# Canbus_controller_-_4.net
KiCad netlist of a schematic drawn in EAGLE
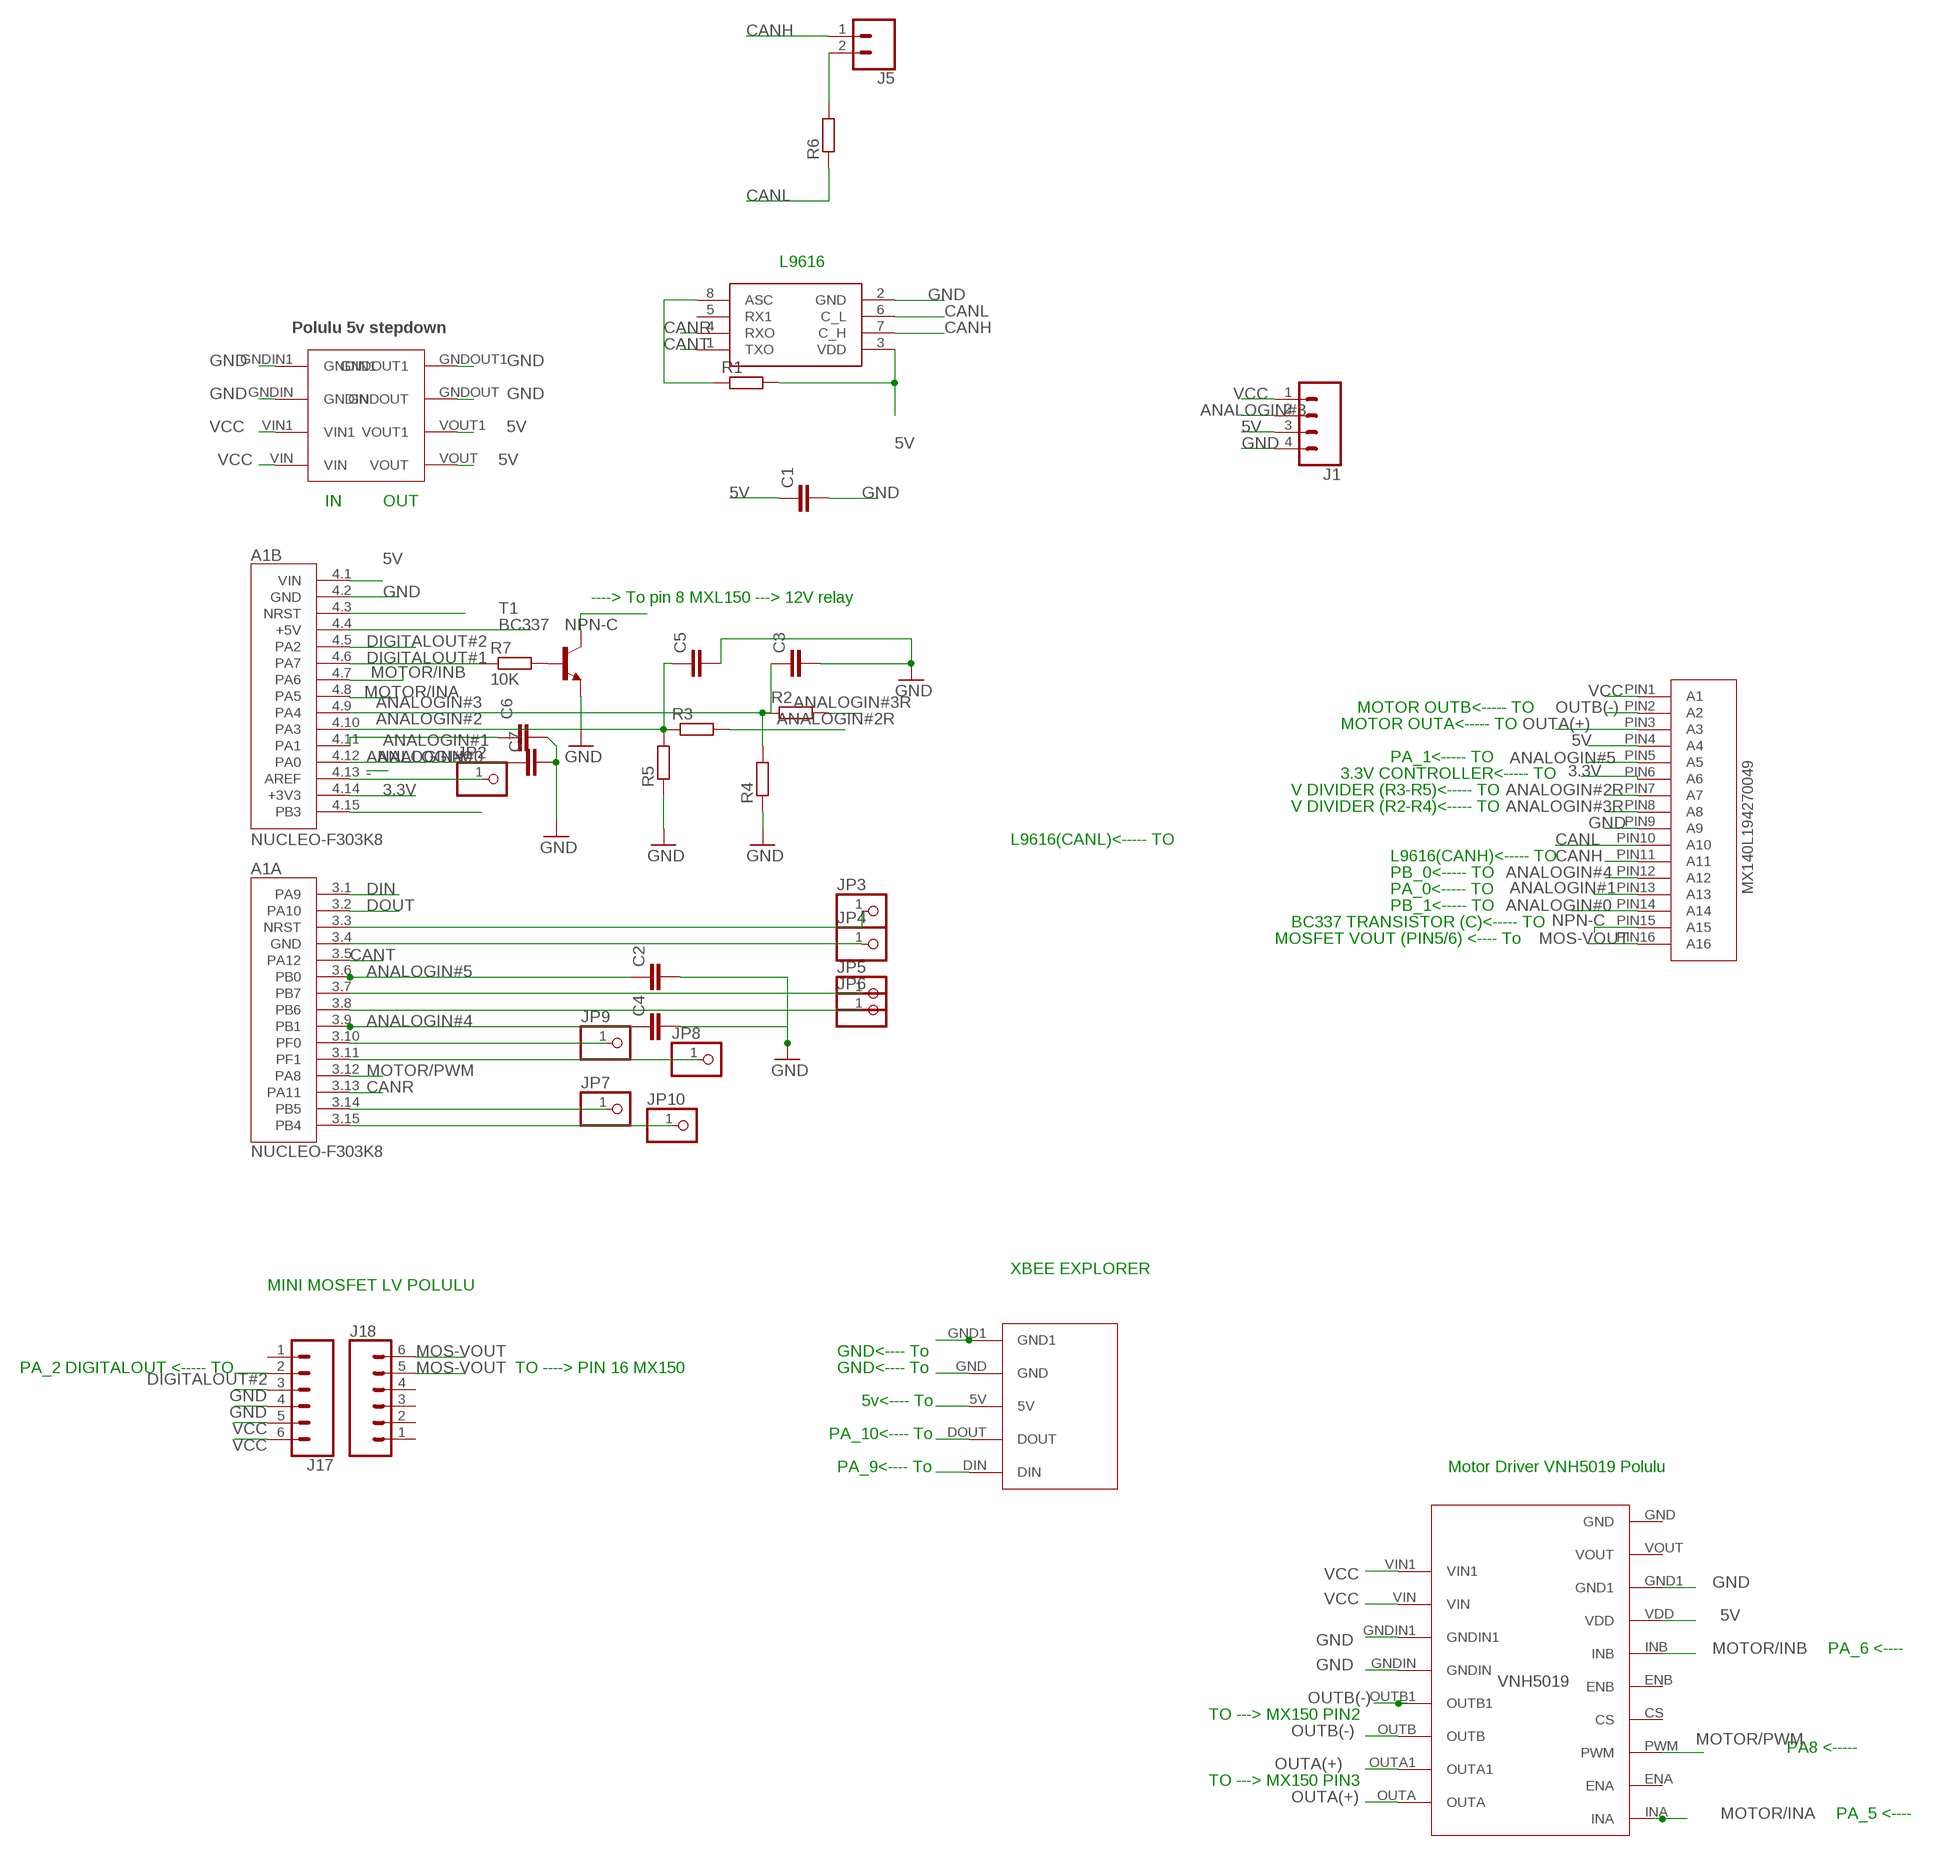
[diagram p0: schematic, sheet 1]

(export (version "E")
  (design (tool "Eeschema 10.0.6"))
  (components
    (comp (ref "A1")
      (value "NUCLEO-F303K8")
      (footprint "eagle-import:MODULE_NUCLEO-F303K8")
      (fields (field (name "MF") "STMicroelectronics"))
      (libsource (lib "eagle-import") (part "NUCLEO-F303K8"))
    )
    (comp (ref "C1")
      (value "C2,5-3")
      (footprint "eagle-import:C2.5-3")
      (libsource (lib "eagle-import") (part "C2,5-3"))
    )
    (comp (ref "C2")
      (value "C-EUC0805")
      (footprint "eagle-import:C0805")
      (libsource (lib "eagle-import") (part "C-EUC0805"))
    )
    (comp (ref "C3")
      (value "C-EUC0805")
      (footprint "eagle-import:C0805")
      (libsource (lib "eagle-import") (part "C-EUC0805"))
    )
    (comp (ref "C4")
      (value "C-EUC0805")
      (footprint "eagle-import:C0805")
      (libsource (lib "eagle-import") (part "C-EUC0805"))
    )
    (comp (ref "C5")
      (value "C-EUC0805")
      (footprint "eagle-import:C0805")
      (libsource (lib "eagle-import") (part "C-EUC0805"))
    )
    (comp (ref "C6")
      (value "C-EUC0805")
      (footprint "eagle-import:C0805")
      (libsource (lib "eagle-import") (part "C-EUC0805"))
    )
    (comp (ref "C7")
      (value "C-EUC0805")
      (footprint "eagle-import:C0805")
      (libsource (lib "eagle-import") (part "C-EUC0805"))
    )
    (comp (ref "J1")
      (value "CONN_04POLAR")
      (footprint "eagle-import:MOLEX-1X4")
      (libsource (lib "eagle-import") (part "CONN_04POLAR"))
    )
    (comp (ref "J5")
      (value "CONN_02")
      (footprint "eagle-import:1X02")
      (libsource (lib "eagle-import") (part "CONN_02"))
    )
    (comp (ref "J17")
      (value "CONN_06NO_SILK_FEMALE_PTH")
      (footprint "eagle-import:1X06_NO_SILK")
      (libsource (lib "eagle-import") (part "CONN_06NO_SILK_FEMALE_PTH"))
    )
    (comp (ref "J18")
      (value "CONN_06NO_SILK_FEMALE_PTH")
      (footprint "eagle-import:1X06_NO_SILK")
      (libsource (lib "eagle-import") (part "CONN_06NO_SILK_FEMALE_PTH"))
    )
    (comp (ref "JP2")
      (value "PINHD-1X1")
      (footprint "eagle-import:1X01")
      (libsource (lib "eagle-import") (part "PINHD-1X1"))
    )
    (comp (ref "JP3")
      (value "PINHD-1X1")
      (footprint "eagle-import:1X01")
      (libsource (lib "eagle-import") (part "PINHD-1X1"))
    )
    (comp (ref "JP4")
      (value "PINHD-1X1")
      (footprint "eagle-import:1X01")
      (libsource (lib "eagle-import") (part "PINHD-1X1"))
    )
    (comp (ref "JP5")
      (value "PINHD-1X1")
      (footprint "eagle-import:1X01")
      (libsource (lib "eagle-import") (part "PINHD-1X1"))
    )
    (comp (ref "JP6")
      (value "PINHD-1X1")
      (footprint "eagle-import:1X01")
      (libsource (lib "eagle-import") (part "PINHD-1X1"))
    )
    (comp (ref "JP7")
      (value "PINHD-1X1")
      (footprint "eagle-import:1X01")
      (libsource (lib "eagle-import") (part "PINHD-1X1"))
    )
    (comp (ref "JP8")
      (value "PINHD-1X1")
      (footprint "eagle-import:1X01")
      (libsource (lib "eagle-import") (part "PINHD-1X1"))
    )
    (comp (ref "JP9")
      (value "PINHD-1X1")
      (footprint "eagle-import:1X01")
      (libsource (lib "eagle-import") (part "PINHD-1X1"))
    )
    (comp (ref "JP10")
      (value "PINHD-1X1")
      (footprint "eagle-import:1X01")
      (libsource (lib "eagle-import") (part "PINHD-1X1"))
    )
    (comp (ref "R1")
      (value "R-EU_0207/7")
      (footprint "eagle-import:0207_7")
      (libsource (lib "eagle-import") (part "R-EU_0207/7"))
    )
    (comp (ref "R2")
      (value "R-EU_0207/7")
      (footprint "eagle-import:0207_7")
      (libsource (lib "eagle-import") (part "R-EU_0207/7"))
    )
    (comp (ref "R3")
      (value "R-EU_0207/7")
      (footprint "eagle-import:0207_7")
      (libsource (lib "eagle-import") (part "R-EU_0207/7"))
    )
    (comp (ref "R4")
      (value "R-EU_0207/7")
      (footprint "eagle-import:0207_7")
      (libsource (lib "eagle-import") (part "R-EU_0207/7"))
    )
    (comp (ref "R5")
      (value "R-EU_0207/7")
      (footprint "eagle-import:0207_7")
      (libsource (lib "eagle-import") (part "R-EU_0207/7"))
    )
    (comp (ref "R6")
      (value "R-EU_0207/7")
      (footprint "eagle-import:0207_7")
      (libsource (lib "eagle-import") (part "R-EU_0207/7"))
    )
    (comp (ref "R7")
      (value "10K")
      (footprint "eagle-import:0207_7")
      (libsource (lib "eagle-import") (part "R-EU_0207/7"))
    )
    (comp (ref "T1")
      (value "BC337")
      (footprint "eagle-import:TO92")
      (libsource (lib "eagle-import") (part "BC337"))
    )
    (comp (ref "U$1")
      (value "L9616")
      (footprint "eagle-import:SO8")
      (fields (field (name "MF") "STMicroelectronics"))
      (libsource (lib "eagle-import") (part "L9616"))
    )
    (comp (ref "U$2")
      (value "MX140L-194270049")
      (footprint "eagle-import:MX150L-194270049")
      (libsource (lib "eagle-import") (part "MX140L-194270049"))
    )
    (comp (ref "U$3")
      (value "XBEEEXPLORER")
      (footprint "eagle-import:XBEEREGULATED")
      (libsource (lib "eagle-import") (part "XBEEEXPLORER"))
    )
    (comp (ref "U$4")
      (value "VNH5019")
      (footprint "eagle-import:VNH5019")
      (libsource (lib "eagle-import") (part "VNH5019"))
    )
    (comp (ref "U$5")
      (value "5VSTEPDOWN")
      (footprint "eagle-import:5VSTEPDOWN")
      (libsource (lib "eagle-import") (part "5VSTEPDOWN"))
    )
  )
  (nets
    (net (code "1") (name "/-") (class "Default")
      (node (ref "A1") (pin "4.13") (pinfunction "AREF_4.13") (pintype "bidirectional"))
      (node (ref "JP2") (pin "1") (pinfunction "1_1") (pintype "passive"))
    )
    (net (code "2") (name "/3.3V") (class "Default")
      (node (ref "A1") (pin "4.14") (pinfunction "+3V3_4.14") (pintype "bidirectional"))
      (node (ref "U$2") (pin "PIN6") (pinfunction "A6_PIN6") (pintype "bidirectional"))
    )
    (net (code "3") (name "/5V") (class "Default")
      (node (ref "A1") (pin "4.1") (pinfunction "VIN_4.1") (pintype "bidirectional"))
      (node (ref "C1") (pin "1") (pinfunction "1_1") (pintype "passive"))
      (node (ref "J1") (pin "3") (pinfunction "3_3") (pintype "passive"))
      (node (ref "R1") (pin "2") (pinfunction "2_2") (pintype "passive"))
      (node (ref "U$1") (pin "3") (pinfunction "VDD_3") (pintype "bidirectional"))
      (node (ref "U$2") (pin "PIN4") (pinfunction "A4_PIN4") (pintype "bidirectional"))
      (node (ref "U$3") (pin "5V") (pinfunction "5V_5V") (pintype "bidirectional"))
      (node (ref "U$4") (pin "VDD") (pinfunction "VDD_VDD") (pintype "bidirectional"))
      (node (ref "U$5") (pin "VOUT") (pinfunction "VOUT_VOUT") (pintype "bidirectional"))
      (node (ref "U$5") (pin "VOUT1") (pinfunction "VOUT1_VOUT1") (pintype "bidirectional"))
    )
    (net (code "4") (name "/ANALOGIN#0") (class "Default")
      (node (ref "A1") (pin "4.12") (pinfunction "PA0_4.12") (pintype "bidirectional"))
      (node (ref "C7") (pin "1") (pinfunction "1_1") (pintype "passive"))
      (node (ref "U$2") (pin "PIN14") (pinfunction "A14_PIN14") (pintype "bidirectional"))
    )
    (net (code "5") (name "/ANALOGIN#1") (class "Default")
      (node (ref "A1") (pin "4.11") (pinfunction "PA1_4.11") (pintype "bidirectional"))
      (node (ref "C6") (pin "1") (pinfunction "1_1") (pintype "passive"))
      (node (ref "U$2") (pin "PIN13") (pinfunction "A13_PIN13") (pintype "bidirectional"))
    )
    (net (code "6") (name "/ANALOGIN#2") (class "Default")
      (node (ref "A1") (pin "4.10") (pinfunction "PA3_4.10") (pintype "bidirectional"))
      (node (ref "C5") (pin "1") (pinfunction "1_1") (pintype "passive"))
      (node (ref "R3") (pin "1") (pinfunction "1_1") (pintype "passive"))
      (node (ref "R5") (pin "2") (pinfunction "2_2") (pintype "passive"))
    )
    (net (code "7") (name "/ANALOGIN#2R") (class "Default")
      (node (ref "R3") (pin "2") (pinfunction "2_2") (pintype "passive"))
      (node (ref "U$2") (pin "PIN7") (pinfunction "A7_PIN7") (pintype "bidirectional"))
    )
    (net (code "8") (name "/ANALOGIN#3") (class "Default")
      (node (ref "A1") (pin "4.9") (pinfunction "PA4_4.9") (pintype "bidirectional"))
      (node (ref "C3") (pin "1") (pinfunction "1_1") (pintype "passive"))
      (node (ref "J1") (pin "2") (pinfunction "2_2") (pintype "passive"))
      (node (ref "R2") (pin "1") (pinfunction "1_1") (pintype "passive"))
      (node (ref "R4") (pin "2") (pinfunction "2_2") (pintype "passive"))
    )
    (net (code "9") (name "/ANALOGIN#3R") (class "Default")
      (node (ref "R2") (pin "2") (pinfunction "2_2") (pintype "passive"))
      (node (ref "U$2") (pin "PIN8") (pinfunction "A8_PIN8") (pintype "bidirectional"))
    )
    (net (code "10") (name "/ANALOGIN#4") (class "Default")
      (node (ref "A1") (pin "3.9") (pinfunction "PB1_3.9") (pintype "bidirectional"))
      (node (ref "C4") (pin "1") (pinfunction "1_1") (pintype "passive"))
      (node (ref "U$2") (pin "PIN12") (pinfunction "A12_PIN12") (pintype "bidirectional"))
    )
    (net (code "11") (name "/ANALOGIN#5") (class "Default")
      (node (ref "A1") (pin "3.6") (pinfunction "PB0_3.6") (pintype "bidirectional"))
      (node (ref "C2") (pin "1") (pinfunction "1_1") (pintype "passive"))
      (node (ref "U$2") (pin "PIN5") (pinfunction "A5_PIN5") (pintype "bidirectional"))
    )
    (net (code "12") (name "/CANH") (class "Default")
      (node (ref "J5") (pin "1") (pinfunction "1_1") (pintype "passive"))
      (node (ref "U$1") (pin "7") (pinfunction "C_H_7") (pintype "bidirectional"))
      (node (ref "U$2") (pin "PIN11") (pinfunction "A11_PIN11") (pintype "bidirectional"))
    )
    (net (code "13") (name "/CANL") (class "Default")
      (node (ref "R6") (pin "1") (pinfunction "1_1") (pintype "passive"))
      (node (ref "U$1") (pin "6") (pinfunction "C_L_6") (pintype "bidirectional"))
      (node (ref "U$2") (pin "PIN10") (pinfunction "A10_PIN10") (pintype "bidirectional"))
    )
    (net (code "14") (name "/CANR") (class "Default")
      (node (ref "A1") (pin "3.13") (pinfunction "PA11_3.13") (pintype "bidirectional"))
      (node (ref "U$1") (pin "4") (pinfunction "RXO_4") (pintype "bidirectional"))
    )
    (net (code "15") (name "/CANT") (class "Default")
      (node (ref "A1") (pin "3.5") (pinfunction "PA12_3.5") (pintype "bidirectional"))
      (node (ref "U$1") (pin "1") (pinfunction "TXO_1") (pintype "bidirectional"))
    )
    (net (code "16") (name "/DIGITALOUT#1") (class "Default")
      (node (ref "A1") (pin "4.6") (pinfunction "PA7_4.6") (pintype "bidirectional"))
      (node (ref "R7") (pin "1") (pinfunction "1_1") (pintype "passive"))
    )
    (net (code "17") (name "/DIGITALOUT#2") (class "Default")
      (node (ref "A1") (pin "4.5") (pinfunction "PA2_4.5") (pintype "bidirectional"))
      (node (ref "J17") (pin "2") (pinfunction "2_2") (pintype "passive"))
    )
    (net (code "18") (name "/DIN") (class "Default")
      (node (ref "A1") (pin "3.1") (pinfunction "PA9_3.1") (pintype "bidirectional"))
      (node (ref "U$3") (pin "DIN") (pinfunction "DIN_DIN") (pintype "bidirectional"))
    )
    (net (code "19") (name "/DOUT") (class "Default")
      (node (ref "A1") (pin "3.2") (pinfunction "PA10_3.2") (pintype "bidirectional"))
      (node (ref "U$3") (pin "DOUT") (pinfunction "DOUT_DOUT") (pintype "bidirectional"))
    )
    (net (code "20") (name "/MOS-VOUT") (class "Default")
      (node (ref "J18") (pin "5") (pinfunction "5_5") (pintype "passive"))
      (node (ref "J18") (pin "6") (pinfunction "6_6") (pintype "passive"))
      (node (ref "U$2") (pin "PIN16") (pinfunction "A16_PIN16") (pintype "bidirectional"))
    )
    (net (code "21") (name "/MOTOR{slash}INA") (class "Default")
      (node (ref "A1") (pin "4.8") (pinfunction "PA5_4.8") (pintype "bidirectional"))
      (node (ref "U$4") (pin "INA") (pinfunction "INA_INA") (pintype "bidirectional"))
    )
    (net (code "22") (name "/MOTOR{slash}INB") (class "Default")
      (node (ref "A1") (pin "4.7") (pinfunction "PA6_4.7") (pintype "bidirectional"))
      (node (ref "U$4") (pin "INB") (pinfunction "INB_INB") (pintype "bidirectional"))
    )
    (net (code "23") (name "/MOTOR{slash}PWM") (class "Default")
      (node (ref "A1") (pin "3.12") (pinfunction "PA8_3.12") (pintype "bidirectional"))
      (node (ref "U$4") (pin "PWM") (pinfunction "PWM_PWM") (pintype "bidirectional"))
    )
    (net (code "24") (name "/NPN-C") (class "Default")
      (node (ref "T1") (pin "3") (pinfunction "C_3") (pintype "passive"))
      (node (ref "U$2") (pin "PIN15") (pinfunction "A15_PIN15") (pintype "bidirectional"))
    )
    (net (code "25") (name "/OUTA(+)") (class "Default")
      (node (ref "U$2") (pin "PIN3") (pinfunction "A3_PIN3") (pintype "bidirectional"))
      (node (ref "U$4") (pin "OUTA") (pinfunction "OUTA_OUTA") (pintype "bidirectional"))
      (node (ref "U$4") (pin "OUTA1") (pinfunction "OUTA1_OUTA1") (pintype "bidirectional"))
    )
    (net (code "26") (name "/OUTB(-)") (class "Default")
      (node (ref "U$2") (pin "PIN2") (pinfunction "A2_PIN2") (pintype "bidirectional"))
      (node (ref "U$4") (pin "OUTB") (pinfunction "OUTB_OUTB") (pintype "bidirectional"))
      (node (ref "U$4") (pin "OUTB1") (pinfunction "OUTB1_OUTB1") (pintype "bidirectional"))
    )
    (net (code "27") (name "/VCC") (class "Default")
      (node (ref "J1") (pin "1") (pinfunction "1_1") (pintype "passive"))
      (node (ref "J17") (pin "5") (pinfunction "5_5") (pintype "passive"))
      (node (ref "J17") (pin "6") (pinfunction "6_6") (pintype "passive"))
      (node (ref "U$2") (pin "PIN1") (pinfunction "A1_PIN1") (pintype "bidirectional"))
      (node (ref "U$4") (pin "VIN") (pinfunction "VIN_VIN") (pintype "bidirectional"))
      (node (ref "U$4") (pin "VIN1") (pinfunction "VIN1_VIN1") (pintype "bidirectional"))
      (node (ref "U$5") (pin "VIN") (pinfunction "VIN_VIN") (pintype "bidirectional"))
      (node (ref "U$5") (pin "VIN1") (pinfunction "VIN1_VIN1") (pintype "bidirectional"))
    )
    (net (code "28") (name "GND") (class "Default")
      (node (ref "A1") (pin "4.2") (pinfunction "GND_4.2") (pintype "bidirectional"))
      (node (ref "C1") (pin "2") (pinfunction "2_2") (pintype "passive"))
      (node (ref "C2") (pin "2") (pinfunction "2_2") (pintype "passive"))
      (node (ref "C3") (pin "2") (pinfunction "2_2") (pintype "passive"))
      (node (ref "C4") (pin "2") (pinfunction "2_2") (pintype "passive"))
      (node (ref "C5") (pin "2") (pinfunction "2_2") (pintype "passive"))
      (node (ref "C6") (pin "2") (pinfunction "2_2") (pintype "passive"))
      (node (ref "C7") (pin "2") (pinfunction "2_2") (pintype "passive"))
      (node (ref "J1") (pin "4") (pinfunction "4_4") (pintype "passive"))
      (node (ref "J17") (pin "3") (pinfunction "3_3") (pintype "passive"))
      (node (ref "J17") (pin "4") (pinfunction "4_4") (pintype "passive"))
      (node (ref "R4") (pin "1") (pinfunction "1_1") (pintype "passive"))
      (node (ref "R5") (pin "1") (pinfunction "1_1") (pintype "passive"))
      (node (ref "T1") (pin "1") (pinfunction "E_1") (pintype "passive"))
      (node (ref "U$1") (pin "2") (pinfunction "GND_2") (pintype "bidirectional"))
      (node (ref "U$2") (pin "PIN9") (pinfunction "A9_PIN9") (pintype "bidirectional"))
      (node (ref "U$3") (pin "GND") (pinfunction "GND_GND") (pintype "bidirectional"))
      (node (ref "U$3") (pin "GND1") (pinfunction "GND1_GND1") (pintype "bidirectional"))
      (node (ref "U$4") (pin "GND1") (pinfunction "GND1_GND1") (pintype "bidirectional"))
      (node (ref "U$4") (pin "GNDIN") (pinfunction "GNDIN_GNDIN") (pintype "bidirectional"))
      (node (ref "U$4") (pin "GNDIN1") (pinfunction "GNDIN1_GNDIN1") (pintype "bidirectional"))
      (node (ref "U$5") (pin "GNDIN") (pinfunction "GNDIN_GNDIN") (pintype "bidirectional"))
      (node (ref "U$5") (pin "GNDIN1") (pinfunction "GNDIN1_GNDIN1") (pintype "bidirectional"))
      (node (ref "U$5") (pin "GNDOUT") (pinfunction "GNDOUT_GNDOUT") (pintype "bidirectional"))
      (node (ref "U$5") (pin "GNDOUT1") (pinfunction "GNDOUT1_GNDOUT1") (pintype "bidirectional"))
    )
    (net (code "29") (name "Net-(A1A-GND)") (class "Default")
      (node (ref "A1") (pin "3.4") (pinfunction "GND_3.4") (pintype "bidirectional"))
      (node (ref "JP4") (pin "1") (pinfunction "1_1") (pintype "passive"))
    )
    (net (code "30") (name "Net-(A1A-NRST)") (class "Default")
      (node (ref "A1") (pin "3.3") (pinfunction "NRST_3.3") (pintype "bidirectional"))
      (node (ref "JP3") (pin "1") (pinfunction "1_1") (pintype "passive"))
    )
    (net (code "31") (name "Net-(A1A-PB4)") (class "Default")
      (node (ref "A1") (pin "3.15") (pinfunction "PB4_3.15") (pintype "bidirectional"))
      (node (ref "JP10") (pin "1") (pinfunction "1_1") (pintype "passive"))
    )
    (net (code "32") (name "Net-(A1A-PB5)") (class "Default")
      (node (ref "A1") (pin "3.14") (pinfunction "PB5_3.14") (pintype "bidirectional"))
      (node (ref "JP7") (pin "1") (pinfunction "1_1") (pintype "passive"))
    )
    (net (code "33") (name "Net-(A1A-PB6)") (class "Default")
      (node (ref "A1") (pin "3.8") (pinfunction "PB6_3.8") (pintype "bidirectional"))
      (node (ref "JP6") (pin "1") (pinfunction "1_1") (pintype "passive"))
    )
    (net (code "34") (name "Net-(A1A-PB7)") (class "Default")
      (node (ref "A1") (pin "3.7") (pinfunction "PB7_3.7") (pintype "bidirectional"))
      (node (ref "JP5") (pin "1") (pinfunction "1_1") (pintype "passive"))
    )
    (net (code "35") (name "Net-(A1A-PF0)") (class "Default")
      (node (ref "A1") (pin "3.10") (pinfunction "PF0_3.10") (pintype "bidirectional"))
      (node (ref "JP9") (pin "1") (pinfunction "1_1") (pintype "passive"))
    )
    (net (code "36") (name "Net-(A1A-PF1)") (class "Default")
      (node (ref "A1") (pin "3.11") (pinfunction "PF1_3.11") (pintype "bidirectional"))
      (node (ref "JP8") (pin "1") (pinfunction "1_1") (pintype "passive"))
    )
    (net (code "37") (name "Net-(J5-Pad2)") (class "Default")
      (node (ref "J5") (pin "2") (pinfunction "2_2") (pintype "passive"))
      (node (ref "R6") (pin "2") (pinfunction "2_2") (pintype "passive"))
    )
    (net (code "38") (name "Net-(T1-B)") (class "Default")
      (node (ref "R7") (pin "2") (pinfunction "2_2") (pintype "passive"))
      (node (ref "T1") (pin "2") (pinfunction "B_2") (pintype "passive"))
    )
    (net (code "39") (name "Net-(U$1-ASC)") (class "Default")
      (node (ref "R1") (pin "1") (pinfunction "1_1") (pintype "passive"))
      (node (ref "U$1") (pin "8") (pinfunction "ASC_8") (pintype "bidirectional"))
    )
    (net (code "40") (name "unconnected-(A1B-+5V-Pad4.4)") (class "Default")
      (node (ref "A1") (pin "4.4") (pinfunction "+5V_4.4") (pintype "bidirectional"))
    )
    (net (code "41") (name "unconnected-(A1B-NRST-Pad4.3)") (class "Default")
      (node (ref "A1") (pin "4.3") (pinfunction "NRST_4.3") (pintype "bidirectional"))
    )
    (net (code "42") (name "unconnected-(A1B-PB3-Pad4.15)") (class "Default")
      (node (ref "A1") (pin "4.15") (pinfunction "PB3_4.15") (pintype "bidirectional"))
    )
    (net (code "43") (name "unconnected-(J17-Pad1)") (class "Default")
      (node (ref "J17") (pin "1") (pinfunction "1_1") (pintype "passive"))
    )
    (net (code "44") (name "unconnected-(J18-Pad1)") (class "Default")
      (node (ref "J18") (pin "1") (pinfunction "1_1") (pintype "passive"))
    )
    (net (code "45") (name "unconnected-(J18-Pad2)") (class "Default")
      (node (ref "J18") (pin "2") (pinfunction "2_2") (pintype "passive"))
    )
    (net (code "46") (name "unconnected-(J18-Pad3)") (class "Default")
      (node (ref "J18") (pin "3") (pinfunction "3_3") (pintype "passive"))
    )
    (net (code "47") (name "unconnected-(J18-Pad4)") (class "Default")
      (node (ref "J18") (pin "4") (pinfunction "4_4") (pintype "passive"))
    )
    (net (code "48") (name "unconnected-(U$1-RX1-Pad5)") (class "Default")
      (node (ref "U$1") (pin "5") (pinfunction "RX1_5") (pintype "bidirectional"))
    )
    (net (code "49") (name "unconnected-(U$4-PadCS)") (class "Default")
      (node (ref "U$4") (pin "CS") (pinfunction "CS_CS") (pintype "bidirectional"))
    )
    (net (code "50") (name "unconnected-(U$4-PadENA)") (class "Default")
      (node (ref "U$4") (pin "ENA") (pinfunction "ENA_ENA") (pintype "bidirectional"))
    )
    (net (code "51") (name "unconnected-(U$4-PadENB)") (class "Default")
      (node (ref "U$4") (pin "ENB") (pinfunction "ENB_ENB") (pintype "bidirectional"))
    )
    (net (code "52") (name "unconnected-(U$4-PadGND)") (class "Default")
      (node (ref "U$4") (pin "GND") (pinfunction "GND_GND") (pintype "bidirectional"))
    )
    (net (code "53") (name "unconnected-(U$4-PadVOUT)") (class "Default")
      (node (ref "U$4") (pin "VOUT") (pinfunction "VOUT_VOUT") (pintype "bidirectional"))
    )
  )
)
